# Charger_Interface_-_CAN.net
KiCad netlist of a schematic drawn in Altium Designer
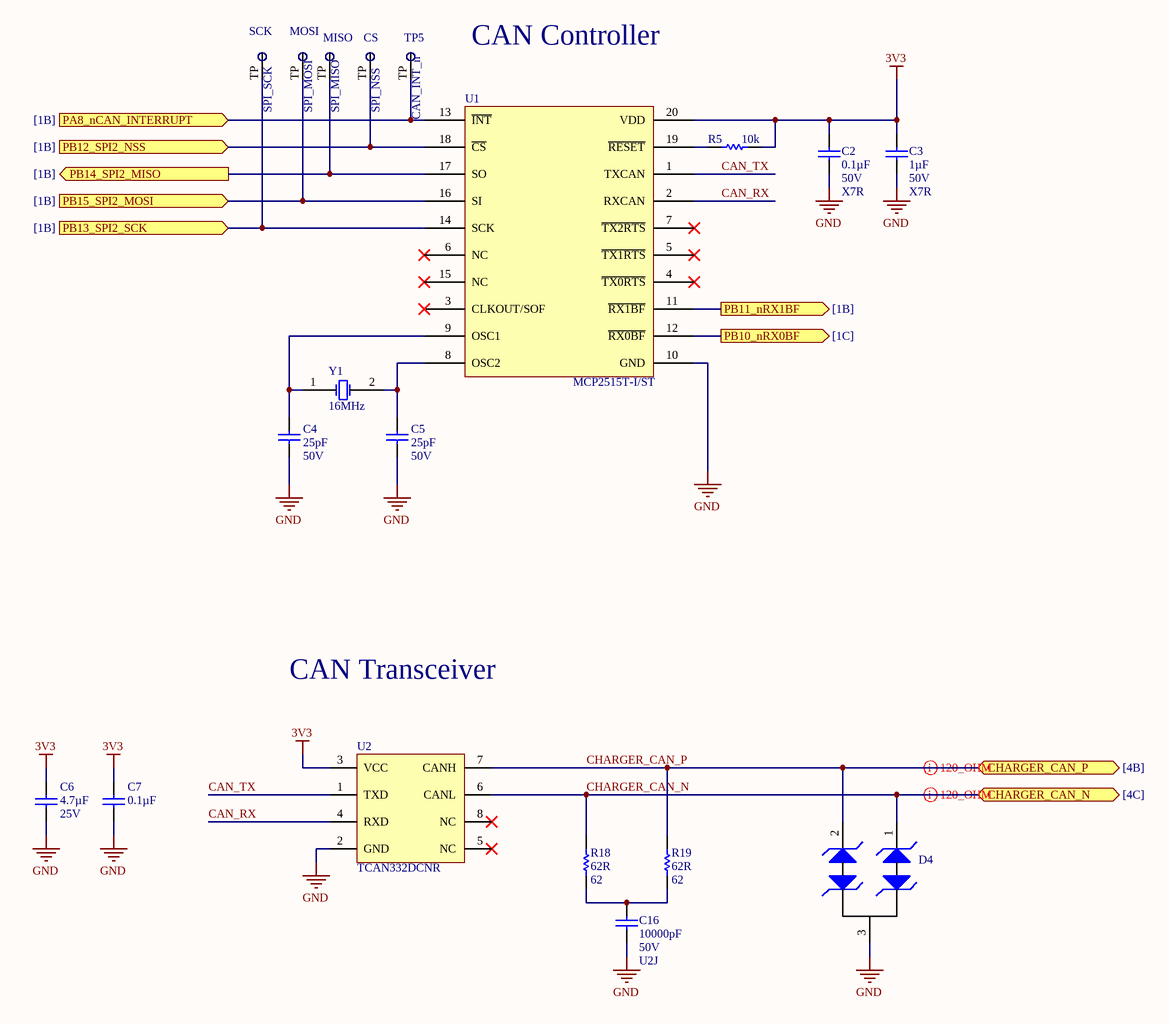
[diagram p0: Charger Interface - CAN.SchDoc]

(export (version "E")
  (design (tool "Eeschema 10.0.6"))
  (components
    (comp (ref "C2")
      (value "CAP CER 0.1UF 50V 10% X7R 0603")
      (footprint "CAP, 0603")
      (description "0.10µF ±10% 50V Ceramic Capacitor X7R 0603 (1608 Metric)")
      (fields
        (field (name "TOLERANCE") "±10%")
        (field (name "CAPACITANCE") "0.1µF")
        (field (name "VOLTAGE") "50V")
        (field (name "TEMPERATURE COEFFICIENT") "X7R")
      )
      (libsource (lib "Schematic Diagrams") (part "CAP CER 0.1UF 50V 10% X7R 0603"))
    )
    (comp (ref "C3")
      (value "CAP CER 1UF 50V 10% X7R 0603")
      (footprint "CAP, 0603")
      (description "1µF ±10% 50V Ceramic Capacitor X7R 0603 (1608 Metric)")
      (fields
        (field (name "TOLERANCE") "±10%")
        (field (name "CAPACITANCE") "1µF")
        (field (name "VOLTAGE") "50V")
        (field (name "TEMPERATURE COEFFICIENT") "X7R")
      )
      (libsource (lib "Schematic Diagrams") (part "CAP CER 1UF 50V 10% X7R 0603"))
    )
    (comp (ref "C4")
      (value "CAP CER 25PF 50V ±5% C0G/NP0 0603")
      (footprint "CAP, 0603")
      (description "25pF 50V Ceramic Capacitor C0G, NP0 0603 (1608 Metric) 0.063\" L x 0.032\" W (1.60mm x 0.80mm)")
      (fields
        (field (name "MANUFACTURER") "Samsung Electro-Mechanics")
        (field (name "MANUFACTURER PART NUMBER") "CL10C250JB8NNNC")
        (field (name "VOLTAGE - RATED") "50V")
        (field (name "CAPACITANCE") "25pF")
      )
      (libsource (lib "Schematic Diagrams") (part "CAP CER 25PF 50V ±5% C0G/NP0 0603"))
    )
    (comp (ref "C5")
      (value "CAP CER 25PF 50V ±5% C0G/NP0 0603")
      (footprint "CAP, 0603")
      (description "25pF 50V Ceramic Capacitor C0G, NP0 0603 (1608 Metric) 0.063\" L x 0.032\" W (1.60mm x 0.80mm)")
      (fields
        (field (name "MANUFACTURER") "Samsung Electro-Mechanics")
        (field (name "MANUFACTURER PART NUMBER") "CL10C250JB8NNNC")
        (field (name "VOLTAGE - RATED") "50V")
        (field (name "CAPACITANCE") "25pF")
      )
      (libsource (lib "Schematic Diagrams") (part "CAP CER 25PF 50V ±5% C0G/NP0 0603"))
    )
    (comp (ref "C6")
      (value "CAP CER 4.7UF 25V 10% X5R 0603")
      (footprint "CAP, 0603")
      (description "4.7µF ±10% 25V Ceramic Capacitor X5R 0603 (1608 Metric)")
      (fields
        (field (name "VOLTAGE") "25V")
        (field (name "TOLERANCE") "±10%")
        (field (name "CAPACITANCE") "4.7µF")
      )
      (libsource (lib "Schematic Diagrams") (part "CAP CER 4.7UF 25V 10% X5R 0603"))
    )
    (comp (ref "C7")
      (value "CAP CER 0.1UF 50V 10% X7R 0603")
      (footprint "CAP, 0603")
      (description "0.10µF ±10% 50V Ceramic Capacitor X7R 0603 (1608 Metric)")
      (fields
        (field (name "VOLTAGE") "50V")
        (field (name "TOLERANCE") "±10%")
        (field (name "CAPACITANCE") "0.1µF")
      )
      (libsource (lib "Schematic Diagrams") (part "CAP CER 0.1UF 50V 10% X7R 0603"))
    )
    (comp (ref "C16")
      (value "CAP CER 10nF 50V 5% X7R 0603")
      (footprint "CAP, 0603")
      (description "10000pF ±5% 50V Ceramic Capacitor U2J 0603 (1608 Metric)")
      (fields
        (field (name "TOLERANCE") "±5%")
        (field (name "CAPACITANCE") "10000pF")
        (field (name "VOLTAGE") "50V")
        (field (name "TEMPERATURE COEFFICIENT") "U2J")
      )
      (libsource (lib "altium-import") (part "root_0_CAP CER 10nF 50V 5% X7R 0603_"))
    )
    (comp (ref "CS")
      (value "SPI_NSS")
      (footprint "Test Point")
      (libsource (lib "Schematic Diagrams") (part "Test Point"))
    )
    (comp (ref "D4")
      (value "DIODE TVS 24VWM 70VC SOT23")
      (footprint "MOSFET P-CH 30V 3.8A SOT-23")
      (description "TVS DIODE 24VWM 70VC SOT23")
      (libsource (lib "altium-import") (part "root_3_DIODE TVS 24VWM 70VC SOT23_"))
    )
    (comp (ref "MISO")
      (value "SPI_MISO")
      (footprint "Test Point")
      (libsource (lib "Schematic Diagrams") (part "Test Point"))
    )
    (comp (ref "MOSI")
      (value "SPI_MOSI")
      (footprint "Test Point")
      (libsource (lib "Schematic Diagrams") (part "Test Point"))
    )
    (comp (ref "R5")
      (value "RES 10K OHM 1% 1/10W 0603")
      (footprint "RES, 0603")
      (description "RES SMD 10K OHM 1% 1/10W 0603")
      (fields
        (field (name "TOLERANCE") "±1%")
        (field (name "RESISTANCE") "10k")
        (field (name "POWER") "1/10W")
      )
      (libsource (lib "Schematic Diagrams") (part "RES 10K OHM 1% 1/10W 0603"))
    )
    (comp (ref "R18")
      (value "62R")
      (footprint "RES, 0603")
      (description "62 Ohms ±0.1% 0.1W, 1/10W Chip Resistor 0603 (1608 Metric) Automotive AEC-Q200 Thin Film")
      (fields
        (field (name "MANUFACTURER") "Panasonic Electronic Components")
        (field (name "MANUFACTURER PART NUMBER") "ERA-3AEB620V")
        (field (name "ALTIUM_VALUE") "62")
      )
      (libsource (lib "altium-import") (part "root_0_RES 62 OHM 0.1% 1/10W 0603_"))
    )
    (comp (ref "R19")
      (value "62R")
      (footprint "RES, 0603")
      (description "62 Ohms ±0.1% 0.1W, 1/10W Chip Resistor 0603 (1608 Metric) Automotive AEC-Q200 Thin Film")
      (fields
        (field (name "MANUFACTURER") "Panasonic Electronic Components")
        (field (name "MANUFACTURER PART NUMBER") "ERA-3AEB620V")
        (field (name "ALTIUM_VALUE") "62")
      )
      (libsource (lib "altium-import") (part "root_0_RES 62 OHM 0.1% 1/10W 0603_"))
    )
    (comp (ref "SCK")
      (value "SPI_SCK")
      (footprint "Test Point")
      (libsource (lib "Schematic Diagrams") (part "Test Point"))
    )
    (comp (ref "TP5")
      (value "CAN_INT_n")
      (footprint "Test Point")
      (libsource (lib "Schematic Diagrams") (part "Test Point"))
    )
    (comp (ref "U1")
      (value "MCP2515")
      (footprint "TSSOP65P640X120-20N")
      (description "CAN Controller CAN 2.0 SPI Interface 20-TSSOP")
      (fields
        (field (name "MANUFACTURER") "Microchip Technology")
        (field (name "MANUFACTURER PART NUMBER") "MCP2515T-I/ST")
      )
      (libsource (lib "altium-import") (part "root_0_IC CAN SPI CONTROLLER MCP2515T-I/ST 20-TSSOP_"))
    )
    (comp (ref "U2")
      (value "IC CAN Tranceiver TCAN332DR")
      (footprint "TSOP65P280X145-8N")
      (description "1/1 Transceiver CANbus SOT-23-8")
      (fields
        (field (name "MANUFACTURER") "Texas Instruments")
        (field (name "MANUFACTURER PART NUMBER") "TCAN332DCNR")
      )
      (libsource (lib "altium-import") (part "root_0_IC CAN Tranceiver TCAN332DR_"))
    )
    (comp (ref "Y1")
      (value "CRYSTAL 16 MHz 18PF 2-SMD")
      (footprint "ABM3 CRYSTAL")
      (description "16MHz ±20ppm Crystal 18pF 40 Ohms 2-SMD, No Lead")
      (fields
        (field (name "MANUFACTURER") "Abracon LLC")
        (field (name "MANUFACTURER PART NUMBER") "ABM3-16.000MHZ-D2Y-T")
        (field (name "FREQUENCY") "16MHz")
      )
      (libsource (lib "Schematic Diagrams") (part "CRYSTAL 16 MHz 18PF 2-SMD"))
    )
  )
  (nets
    (net (code "1") (name "/CAN_RX") (class "Default")
      (node (ref "U1") (pin "2") (pinfunction "RXCAN_2") (pintype "passive"))
      (node (ref "U2") (pin "4") (pinfunction "RXD_4") (pintype "passive"))
    )
    (net (code "2") (name "/CAN_TX") (class "Default")
      (node (ref "U1") (pin "1") (pinfunction "TXCAN_1") (pintype "passive"))
      (node (ref "U2") (pin "1") (pinfunction "TXD_1") (pintype "passive"))
    )
    (net (code "3") (name "/CHARGER_CAN_N") (class "Default")
      (node (ref "D4") (pin "1") (pinfunction "Cathode1_1") (pintype "passive"))
      (node (ref "R18") (pin "1") (pinfunction "1_1") (pintype "passive"))
      (node (ref "U2") (pin "6") (pinfunction "CANL_6") (pintype "passive"))
    )
    (net (code "4") (name "/CHARGER_CAN_P") (class "Default")
      (node (ref "D4") (pin "2") (pinfunction "Cathode2_2") (pintype "passive"))
      (node (ref "R19") (pin "1") (pinfunction "1_1") (pintype "passive"))
      (node (ref "U2") (pin "7") (pinfunction "CANH_7") (pintype "passive"))
    )
    (net (code "5") (name "/PA8_nCAN_INTERRUPT") (class "Default")
      (node (ref "TP5") (pin "TP") (pinfunction "1_TP") (pintype "passive"))
      (node (ref "U1") (pin "13") (pinfunction "~{INT}_13") (pintype "passive"))
    )
    (net (code "6") (name "/PB10_nRX0BF") (class "Default")
      (node (ref "U1") (pin "12") (pinfunction "~{RX0BF}_12") (pintype "passive"))
    )
    (net (code "7") (name "/PB11_nRX1BF") (class "Default")
      (node (ref "U1") (pin "11") (pinfunction "~{RX1BF}_11") (pintype "passive"))
    )
    (net (code "8") (name "/PB12_SPI2_NSS") (class "Default")
      (node (ref "CS") (pin "TP") (pinfunction "1_TP") (pintype "passive"))
      (node (ref "U1") (pin "18") (pinfunction "~{CS}_18") (pintype "passive"))
    )
    (net (code "9") (name "/PB13_SPI2_SCK") (class "Default")
      (node (ref "SCK") (pin "TP") (pinfunction "1_TP") (pintype "passive"))
      (node (ref "U1") (pin "14") (pinfunction "SCK_14") (pintype "passive"))
    )
    (net (code "10") (name "/PB14_SPI2_MISO") (class "Default")
      (node (ref "MISO") (pin "TP") (pinfunction "1_TP") (pintype "passive"))
      (node (ref "U1") (pin "17") (pinfunction "SO_17") (pintype "passive"))
    )
    (net (code "11") (name "/PB15_SPI2_MOSI") (class "Default")
      (node (ref "MOSI") (pin "TP") (pinfunction "1_TP") (pintype "passive"))
      (node (ref "U1") (pin "16") (pinfunction "SI_16") (pintype "passive"))
    )
    (net (code "12") (name "3V3") (class "Default")
      (node (ref "C2") (pin "1") (pinfunction "1_1") (pintype "passive"))
      (node (ref "C3") (pin "1") (pinfunction "1_1") (pintype "passive"))
      (node (ref "C6") (pin "2") (pinfunction "2_2") (pintype "passive"))
      (node (ref "C7") (pin "2") (pinfunction "2_2") (pintype "passive"))
      (node (ref "R5") (pin "2") (pinfunction "2_2") (pintype "passive"))
      (node (ref "U1") (pin "20") (pinfunction "VDD_20") (pintype "passive"))
      (node (ref "U2") (pin "3") (pinfunction "VCC_3") (pintype "passive"))
    )
    (net (code "13") (name "GND") (class "Default")
      (node (ref "C16") (pin "2") (pinfunction "2_2") (pintype "passive"))
      (node (ref "C2") (pin "2") (pinfunction "2_2") (pintype "passive"))
      (node (ref "C3") (pin "2") (pinfunction "2_2") (pintype "passive"))
      (node (ref "C4") (pin "2") (pinfunction "2_2") (pintype "passive"))
      (node (ref "C5") (pin "2") (pinfunction "2_2") (pintype "passive"))
      (node (ref "C6") (pin "1") (pinfunction "1_1") (pintype "passive"))
      (node (ref "C7") (pin "1") (pinfunction "1_1") (pintype "passive"))
      (node (ref "D4") (pin "3") (pinfunction "Common_Cathode_3") (pintype "power_in"))
      (node (ref "U1") (pin "10") (pinfunction "GND_10") (pintype "passive"))
      (node (ref "U2") (pin "2") (pinfunction "GND_2") (pintype "passive"))
    )
    (net (code "14") (name "Net-(C16-Pad1)") (class "Default")
      (node (ref "C16") (pin "1") (pinfunction "1_1") (pintype "passive"))
      (node (ref "R18") (pin "2") (pinfunction "2_2") (pintype "passive"))
      (node (ref "R19") (pin "2") (pinfunction "2_2") (pintype "passive"))
    )
    (net (code "15") (name "Net-(U1-OSC1)") (class "Default")
      (node (ref "C4") (pin "1") (pinfunction "1_1") (pintype "passive"))
      (node (ref "U1") (pin "9") (pinfunction "OSC1_9") (pintype "passive"))
      (node (ref "Y1") (pin "1") (pinfunction "1_1") (pintype "passive"))
    )
    (net (code "16") (name "Net-(U1-OSC2)") (class "Default")
      (node (ref "C5") (pin "1") (pinfunction "1_1") (pintype "passive"))
      (node (ref "U1") (pin "8") (pinfunction "OSC2_8") (pintype "passive"))
      (node (ref "Y1") (pin "2") (pinfunction "2_2") (pintype "passive"))
    )
    (net (code "17") (name "Net-(U1-~{RESET})") (class "Default")
      (node (ref "R5") (pin "1") (pinfunction "1_1") (pintype "passive"))
      (node (ref "U1") (pin "19") (pinfunction "~{RESET}_19") (pintype "passive"))
    )
    (net (code "18") (name "unconnected-(U1-CLKOUT{slash}SOF-Pad3)") (class "Default")
      (node (ref "U1") (pin "3") (pinfunction "CLKOUT/SOF_3") (pintype "passive+no_connect"))
    )
    (net (code "19") (name "unconnected-(U1-NC-Pad6)") (class "Default")
      (node (ref "U1") (pin "6") (pinfunction "NC_6") (pintype "passive+no_connect"))
    )
    (net (code "20") (name "unconnected-(U1-NC-Pad15)") (class "Default")
      (node (ref "U1") (pin "15") (pinfunction "NC_15") (pintype "passive+no_connect"))
    )
    (net (code "21") (name "unconnected-(U1-~{TX0RTS}-Pad4)") (class "Default")
      (node (ref "U1") (pin "4") (pinfunction "~{TX0RTS}_4") (pintype "passive+no_connect"))
    )
    (net (code "22") (name "unconnected-(U1-~{TX1RTS}-Pad5)") (class "Default")
      (node (ref "U1") (pin "5") (pinfunction "~{TX1RTS}_5") (pintype "passive+no_connect"))
    )
    (net (code "23") (name "unconnected-(U1-~{TX2RTS}-Pad7)") (class "Default")
      (node (ref "U1") (pin "7") (pinfunction "~{TX2RTS}_7") (pintype "passive+no_connect"))
    )
    (net (code "24") (name "unconnected-(U2-NC-Pad5)") (class "Default")
      (node (ref "U2") (pin "5") (pinfunction "NC_5") (pintype "passive+no_connect"))
    )
    (net (code "25") (name "unconnected-(U2-NC-Pad8)") (class "Default")
      (node (ref "U2") (pin "8") (pinfunction "NC_8") (pintype "passive+no_connect"))
    )
  )
)
